# THS7001_PGA.net
KiCad netlist of a schematic drawn in Altium Designer
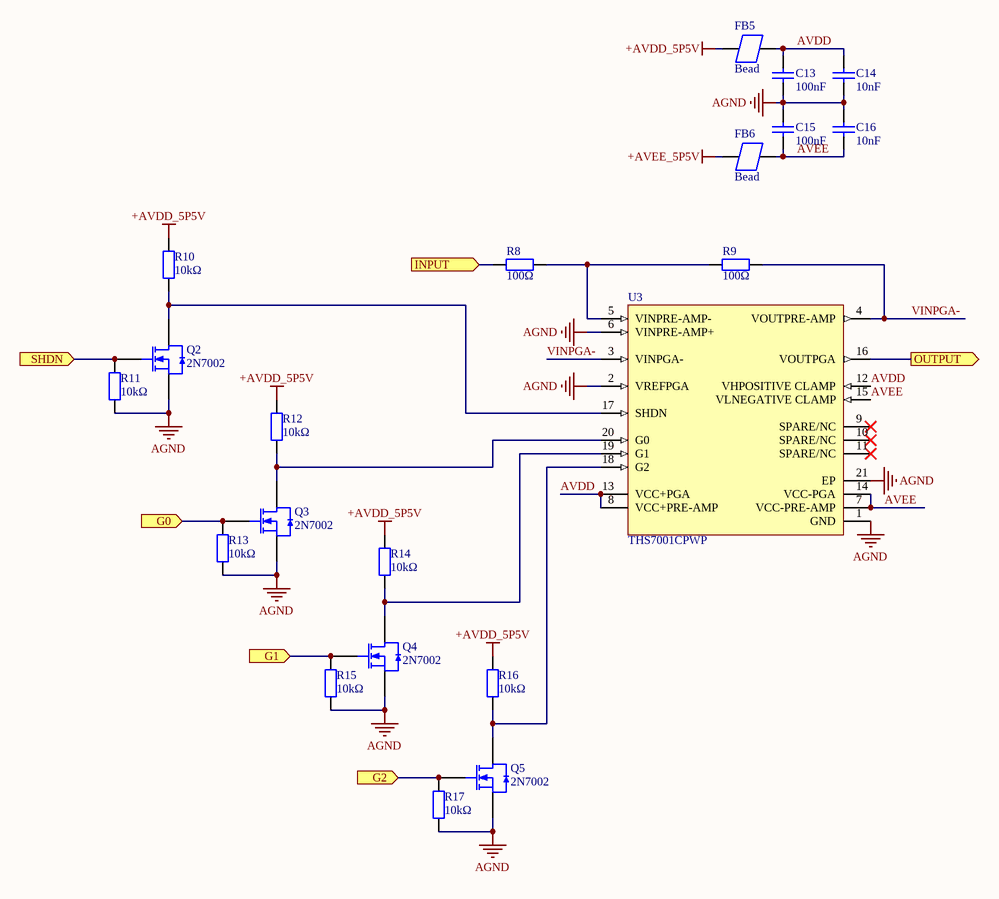
[diagram p0: THS7001_PGA.SchDoc]

(export (version "E")
  (design (tool "Eeschema 10.0.6"))
  (components
    (comp (ref "C13")
      (value "100nF")
      (footprint "0603_C")
      (description "贴片电容")
      (libsource (lib "Miscellaneous Devices LC") (part "0603 100nF (104) 10% 50V"))
    )
    (comp (ref "C14")
      (value "10nF")
      (footprint "0603_C")
      (description "贴片电容")
      (libsource (lib "Miscellaneous Devices LC") (part "0603 10nF (103) 10% 50V"))
    )
    (comp (ref "C15")
      (value "100nF")
      (footprint "0603_C")
      (description "贴片电容")
      (libsource (lib "Miscellaneous Devices LC") (part "0603 100nF (104) 10% 50V"))
    )
    (comp (ref "C16")
      (value "10nF")
      (footprint "0603_C")
      (description "贴片电容")
      (libsource (lib "Miscellaneous Devices LC") (part "0603 10nF (103) 10% 50V"))
    )
    (comp (ref "FB5") (value "Bead") (footprint "0805_L") (libsource (lib "OlvkLib") (part "Bead")))
    (comp (ref "FB6") (value "Bead") (footprint "0805_L") (libsource (lib "OlvkLib") (part "Bead")))
    (comp (ref "Q2")
      (value "2N7002")
      (footprint "SOT-23(SOT-23-3)")
      (description "MOS(场效应管)")
      (libsource (lib "Miscellaneous Devices LC") (part "2N7002 7002"))
    )
    (comp (ref "Q3")
      (value "2N7002")
      (footprint "SOT-23(SOT-23-3)")
      (description "MOS(场效应管)")
      (libsource (lib "Miscellaneous Devices LC") (part "2N7002 7002"))
    )
    (comp (ref "Q4")
      (value "2N7002")
      (footprint "SOT-23(SOT-23-3)")
      (description "MOS(场效应管)")
      (libsource (lib "Miscellaneous Devices LC") (part "2N7002 7002"))
    )
    (comp (ref "Q5")
      (value "2N7002")
      (footprint "SOT-23(SOT-23-3)")
      (description "MOS(场效应管)")
      (libsource (lib "Miscellaneous Devices LC") (part "2N7002 7002"))
    )
    (comp (ref "R8")
      (value "100Ω")
      (footprint "0603_R")
      (description "贴片电阻")
      (libsource (lib "Miscellaneous Devices LC") (part "0603 100Ω (1000) 1%"))
    )
    (comp (ref "R9")
      (value "100Ω")
      (footprint "0603_R")
      (description "贴片电阻")
      (libsource (lib "Miscellaneous Devices LC") (part "0603 100Ω (1000) 1%"))
    )
    (comp (ref "R10")
      (value "10kΩ")
      (footprint "0603_R")
      (description "贴片电阻")
      (libsource (lib "Miscellaneous Devices LC") (part "0603 10KΩ (1002) 1%"))
    )
    (comp (ref "R11")
      (value "10kΩ")
      (footprint "0603_R")
      (description "贴片电阻")
      (libsource (lib "Miscellaneous Devices LC") (part "0603 10KΩ (1002) 1%"))
    )
    (comp (ref "R12")
      (value "10kΩ")
      (footprint "0603_R")
      (description "贴片电阻")
      (libsource (lib "Miscellaneous Devices LC") (part "0603 10KΩ (1002) 1%"))
    )
    (comp (ref "R13")
      (value "10kΩ")
      (footprint "0603_R")
      (description "贴片电阻")
      (libsource (lib "Miscellaneous Devices LC") (part "0603 10KΩ (1002) 1%"))
    )
    (comp (ref "R14")
      (value "10kΩ")
      (footprint "0603_R")
      (description "贴片电阻")
      (libsource (lib "Miscellaneous Devices LC") (part "0603 10KΩ (1002) 1%"))
    )
    (comp (ref "R15")
      (value "10kΩ")
      (footprint "0603_R")
      (description "贴片电阻")
      (libsource (lib "Miscellaneous Devices LC") (part "0603 10KΩ (1002) 1%"))
    )
    (comp (ref "R16")
      (value "10kΩ")
      (footprint "0603_R")
      (description "贴片电阻")
      (libsource (lib "Miscellaneous Devices LC") (part "0603 10KΩ (1002) 1%"))
    )
    (comp (ref "R17")
      (value "10kΩ")
      (footprint "0603_R")
      (description "贴片电阻")
      (libsource (lib "Miscellaneous Devices LC") (part "0603 10KΩ (1002) 1%"))
    )
    (comp (ref "U3")
      (value "THS7001CPWP")
      (footprint "PWP0020D_M")
      (fields (field (name "MANUFACTURER") "Texas Instruments"))
      (libsource (lib "Altium Content Vault") (part "TI-THS7001PWP20-3005X2005TP"))
    )
  )
  (nets
    (net (code "1") (name "+AVDD_5P5V") (class "Default")
      (node (ref "FB5") (pin "1") (pinfunction "1_1") (pintype "passive"))
      (node (ref "R10") (pin "2") (pinfunction "2_2") (pintype "passive"))
      (node (ref "R12") (pin "2") (pinfunction "2_2") (pintype "passive"))
      (node (ref "R14") (pin "2") (pinfunction "2_2") (pintype "passive"))
      (node (ref "R16") (pin "2") (pinfunction "2_2") (pintype "passive"))
    )
    (net (code "2") (name "+AVEE_5P5V") (class "Default")
      (node (ref "FB6") (pin "1") (pinfunction "1_1") (pintype "passive"))
    )
    (net (code "3") (name "/AVDD") (class "Default")
      (node (ref "C13") (pin "2") (pinfunction "2_2") (pintype "passive"))
      (node (ref "C14") (pin "2") (pinfunction "2_2") (pintype "passive"))
      (node (ref "FB5") (pin "2") (pinfunction "2_2") (pintype "passive"))
      (node (ref "U3") (pin "12") (pinfunction "VHPOSITIVE_CLAMP_12") (pintype "input"))
      (node (ref "U3") (pin "13") (pinfunction "VCC+PGA_13") (pintype "power_in"))
      (node (ref "U3") (pin "8") (pinfunction "VCC+PRE-AMP_8") (pintype "power_in"))
    )
    (net (code "4") (name "/AVEE") (class "Default")
      (node (ref "C15") (pin "2") (pinfunction "2_2") (pintype "passive"))
      (node (ref "C16") (pin "2") (pinfunction "2_2") (pintype "passive"))
      (node (ref "FB6") (pin "2") (pinfunction "2_2") (pintype "passive"))
      (node (ref "U3") (pin "14") (pinfunction "VCC-PGA_14") (pintype "power_in"))
      (node (ref "U3") (pin "15") (pinfunction "VLNEGATIVE_CLAMP_15") (pintype "input"))
      (node (ref "U3") (pin "7") (pinfunction "VCC-PRE-AMP_7") (pintype "power_in"))
    )
    (net (code "5") (name "/G0") (class "Default")
      (node (ref "Q3") (pin "1") (pinfunction "G_1") (pintype "passive"))
      (node (ref "R13") (pin "2") (pinfunction "2_2") (pintype "passive"))
    )
    (net (code "6") (name "/G1") (class "Default")
      (node (ref "Q4") (pin "1") (pinfunction "G_1") (pintype "passive"))
      (node (ref "R15") (pin "2") (pinfunction "2_2") (pintype "passive"))
    )
    (net (code "7") (name "/G2") (class "Default")
      (node (ref "Q5") (pin "1") (pinfunction "G_1") (pintype "passive"))
      (node (ref "R17") (pin "2") (pinfunction "2_2") (pintype "passive"))
    )
    (net (code "8") (name "/INPUT") (class "Default")
      (node (ref "R8") (pin "1") (pinfunction "1_1") (pintype "passive"))
    )
    (net (code "9") (name "/OUTPUT") (class "Default")
      (node (ref "U3") (pin "16") (pinfunction "VOUTPGA_16") (pintype "output"))
    )
    (net (code "10") (name "/SHDN") (class "Default")
      (node (ref "Q2") (pin "1") (pinfunction "G_1") (pintype "passive"))
      (node (ref "R11") (pin "2") (pinfunction "2_2") (pintype "passive"))
    )
    (net (code "11") (name "/VINPGA-") (class "Default")
      (node (ref "R9") (pin "2") (pinfunction "2_2") (pintype "passive"))
      (node (ref "U3") (pin "3") (pinfunction "VINPGA-_3") (pintype "input"))
      (node (ref "U3") (pin "4") (pinfunction "VOUTPRE-AMP_4") (pintype "output"))
    )
    (net (code "12") (name "AGND") (class "Default")
      (node (ref "C13") (pin "1") (pinfunction "1_1") (pintype "passive"))
      (node (ref "C14") (pin "1") (pinfunction "1_1") (pintype "passive"))
      (node (ref "C15") (pin "1") (pinfunction "1_1") (pintype "passive"))
      (node (ref "C16") (pin "1") (pinfunction "1_1") (pintype "passive"))
      (node (ref "Q2") (pin "2") (pinfunction "S_2") (pintype "passive"))
      (node (ref "Q3") (pin "2") (pinfunction "S_2") (pintype "passive"))
      (node (ref "Q4") (pin "2") (pinfunction "S_2") (pintype "passive"))
      (node (ref "Q5") (pin "2") (pinfunction "S_2") (pintype "passive"))
      (node (ref "R11") (pin "1") (pinfunction "1_1") (pintype "passive"))
      (node (ref "R13") (pin "1") (pinfunction "1_1") (pintype "passive"))
      (node (ref "R15") (pin "1") (pinfunction "1_1") (pintype "passive"))
      (node (ref "R17") (pin "1") (pinfunction "1_1") (pintype "passive"))
      (node (ref "U3") (pin "1") (pinfunction "GND_1") (pintype "power_in"))
      (node (ref "U3") (pin "2") (pinfunction "VREFPGA_2") (pintype "input"))
      (node (ref "U3") (pin "21") (pinfunction "EP_21") (pintype "power_in"))
      (node (ref "U3") (pin "6") (pinfunction "VINPRE-AMP+_6") (pintype "input"))
    )
    (net (code "13") (name "Net-(Q2-D)") (class "Default")
      (node (ref "Q2") (pin "3") (pinfunction "D_3") (pintype "passive"))
      (node (ref "R10") (pin "1") (pinfunction "1_1") (pintype "passive"))
      (node (ref "U3") (pin "17") (pinfunction "SHDN_17") (pintype "input"))
    )
    (net (code "14") (name "Net-(Q3-D)") (class "Default")
      (node (ref "Q3") (pin "3") (pinfunction "D_3") (pintype "passive"))
      (node (ref "R12") (pin "1") (pinfunction "1_1") (pintype "passive"))
      (node (ref "U3") (pin "20") (pinfunction "G0_20") (pintype "input"))
    )
    (net (code "15") (name "Net-(Q4-D)") (class "Default")
      (node (ref "Q4") (pin "3") (pinfunction "D_3") (pintype "passive"))
      (node (ref "R14") (pin "1") (pinfunction "1_1") (pintype "passive"))
      (node (ref "U3") (pin "19") (pinfunction "G1_19") (pintype "input"))
    )
    (net (code "16") (name "Net-(Q5-D)") (class "Default")
      (node (ref "Q5") (pin "3") (pinfunction "D_3") (pintype "passive"))
      (node (ref "R16") (pin "1") (pinfunction "1_1") (pintype "passive"))
      (node (ref "U3") (pin "18") (pinfunction "G2_18") (pintype "input"))
    )
    (net (code "17") (name "Net-(U3-VINPRE-AMP-)") (class "Default")
      (node (ref "R8") (pin "2") (pinfunction "2_2") (pintype "passive"))
      (node (ref "R9") (pin "1") (pinfunction "1_1") (pintype "passive"))
      (node (ref "U3") (pin "5") (pinfunction "VINPRE-AMP-_5") (pintype "input"))
    )
    (net (code "18") (name "unconnected-(U3-SPARE{slash}NC-Pad9)") (class "Default")
      (node (ref "U3") (pin "9") (pinfunction "SPARE/NC_9") (pintype "passive+no_connect"))
    )
    (net (code "19") (name "unconnected-(U3-SPARE{slash}NC-Pad10)") (class "Default")
      (node (ref "U3") (pin "10") (pinfunction "SPARE/NC_10") (pintype "passive+no_connect"))
    )
    (net (code "20") (name "unconnected-(U3-SPARE{slash}NC-Pad11)") (class "Default")
      (node (ref "U3") (pin "11") (pinfunction "SPARE/NC_11") (pintype "passive+no_connect"))
    )
  )
)
